# igvv.net
KiCad netlist of a schematic drawn in EAGLE
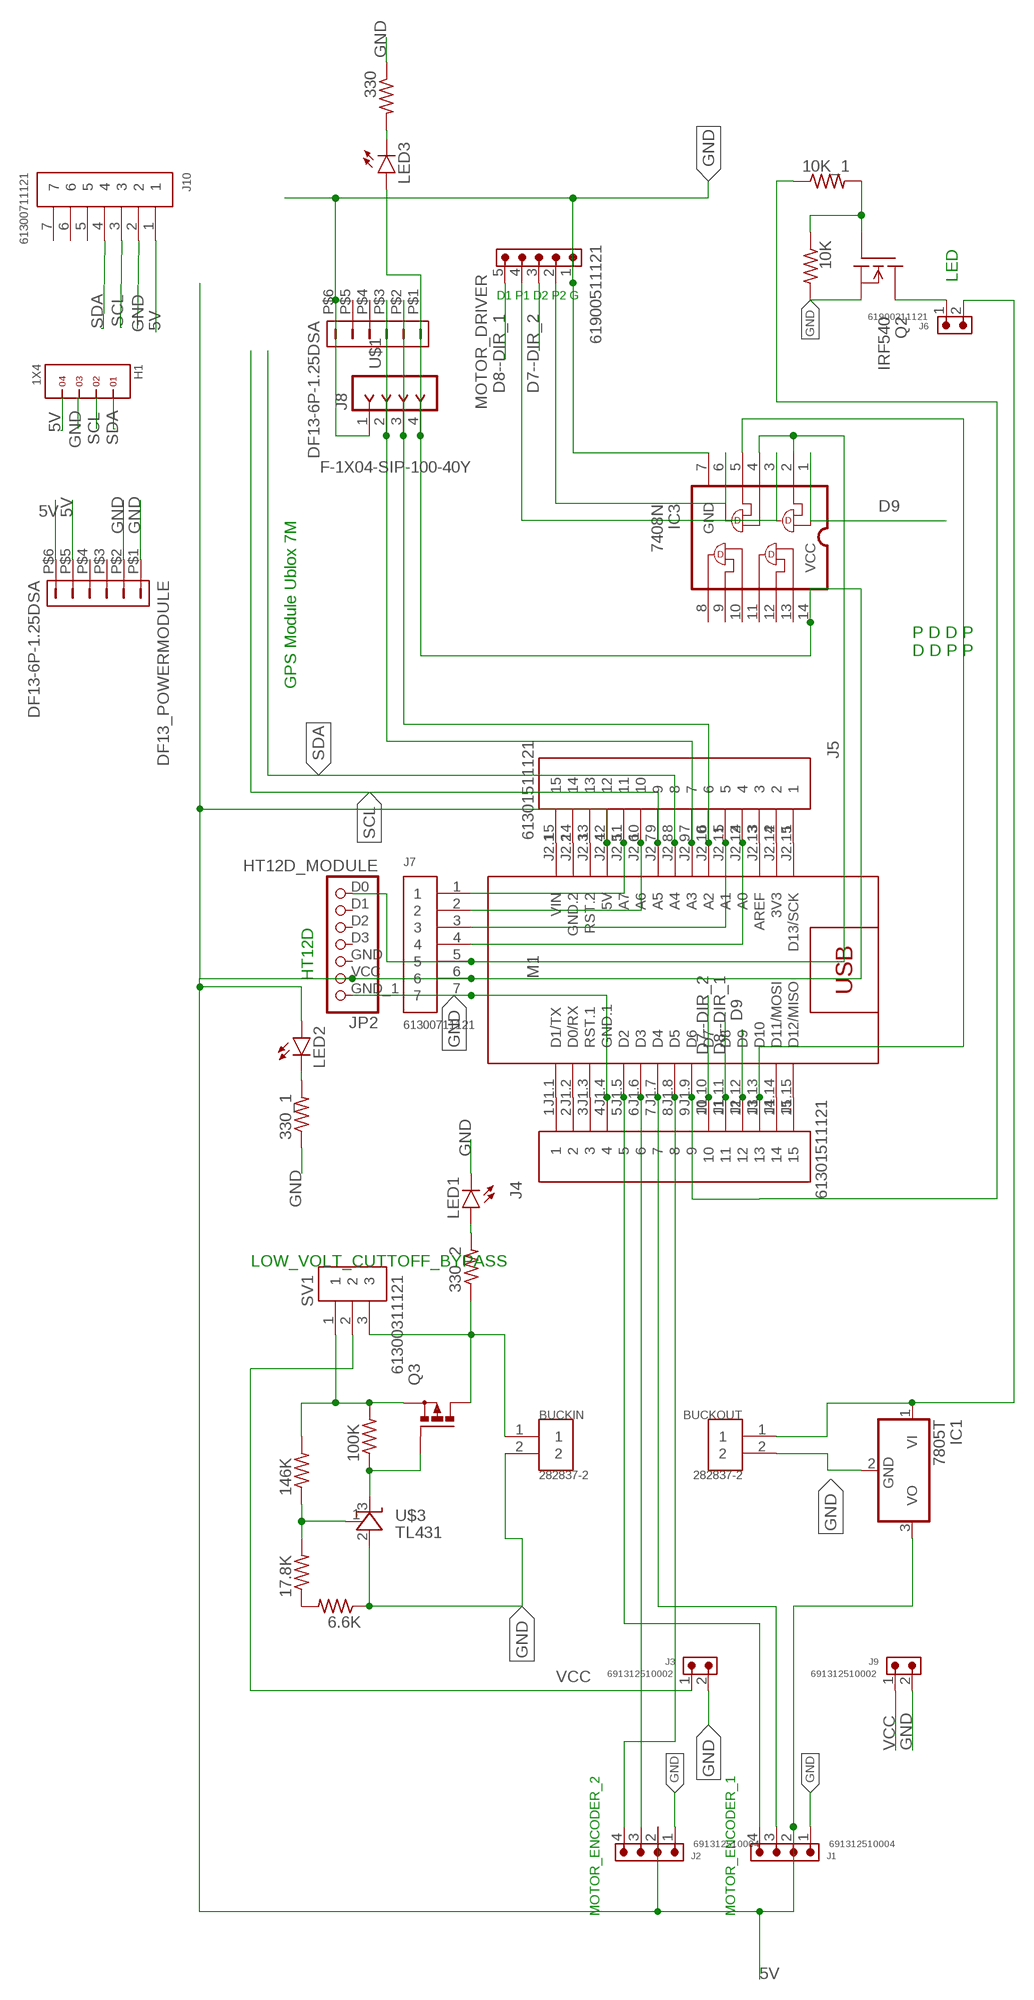
[diagram p0: schematic, sheet 1]

(export (version "E")
  (design (tool "Eeschema 10.0.6"))
  (components
    (comp (ref "6.6K")
      (value "R-US_0207/10")
      (footprint "eagle-import:0207_10")
      (libsource (lib "eagle-import") (part "R-US_0207/10"))
    )
    (comp (ref "10K")
      (value "R-US_0207/10")
      (footprint "eagle-import:0207_10")
      (libsource (lib "eagle-import") (part "R-US_0207/10"))
    )
    (comp (ref "10K_1")
      (value "R-US_0207/10")
      (footprint "eagle-import:0207_10")
      (libsource (lib "eagle-import") (part "R-US_0207/10"))
    )
    (comp (ref "17.8K")
      (value "R-US_0207/10")
      (footprint "eagle-import:0207_10")
      (libsource (lib "eagle-import") (part "R-US_0207/10"))
    )
    (comp (ref "100K")
      (value "R-US_0207/10")
      (footprint "eagle-import:0207_10")
      (libsource (lib "eagle-import") (part "R-US_0207/10"))
    )
    (comp (ref "146K")
      (value "R-US_0207/10")
      (footprint "eagle-import:0207_10")
      (libsource (lib "eagle-import") (part "R-US_0207/10"))
    )
    (comp (ref "330")
      (value "R-US_0207/10")
      (footprint "eagle-import:0207_10")
      (libsource (lib "eagle-import") (part "R-US_0207/10"))
    )
    (comp (ref "330_1")
      (value "R-US_0207/10")
      (footprint "eagle-import:0207_10")
      (libsource (lib "eagle-import") (part "R-US_0207/10"))
    )
    (comp (ref "330_2")
      (value "R-US_0207/10")
      (footprint "eagle-import:0207_10")
      (libsource (lib "eagle-import") (part "R-US_0207/10"))
    )
    (comp (ref "BUCKIN")
      (value "282837-2")
      (footprint "eagle-import:TE_282837-2")
      (fields (field (name "MF") "TE Connectivity"))
      (libsource (lib "eagle-import") (part "282837-2"))
    )
    (comp (ref "BUCKOUT")
      (value "282837-2")
      (footprint "eagle-import:TE_282837-2")
      (fields (field (name "MF") "TE Connectivity"))
      (libsource (lib "eagle-import") (part "282837-2"))
    )
    (comp (ref "DF13_POWERMODULE")
      (value "DF13-6P-1.25DSA")
      (footprint "eagle-import:DF13-6P-1.25DSA")
      (libsource (lib "eagle-import") (part "DF13-6P-1.25DSA"))
    )
    (comp (ref "H1")
      (value "1X4")
      (footprint "eagle-import:1X4")
      (libsource (lib "eagle-import") (part "1X4"))
    )
    (comp (ref "IC1")
      (value "7805T")
      (footprint "eagle-import:TO220H")
      (libsource (lib "eagle-import") (part "7805T"))
    )
    (comp (ref "IC3")
      (value "7408N")
      (footprint "eagle-import:DIL14")
      (libsource (lib "eagle-import") (part "7408N"))
    )
    (comp (ref "J1")
      (value "691312510004")
      (footprint "eagle-import:691312510004")
      (libsource (lib "eagle-import") (part "691312510004"))
    )
    (comp (ref "J2")
      (value "691312510004")
      (footprint "eagle-import:691312510004")
      (libsource (lib "eagle-import") (part "691312510004"))
    )
    (comp (ref "J3")
      (value "691312510002")
      (footprint "eagle-import:691312510002")
      (libsource (lib "eagle-import") (part "691312510002"))
    )
    (comp (ref "J4")
      (value "61301511121")
      (footprint "eagle-import:61301511121")
      (fields
        (field (name "DIGIKEY_PART_NUMBER") "732-5326-ND")
        (field (name "MANUFACTURER") "Wurth Electronics Inc.")
        (field (name "CREATED_BY") "PCBLayout.com")
      )
      (libsource (lib "eagle-import") (part "61301511121"))
    )
    (comp (ref "J5")
      (value "61301511121")
      (footprint "eagle-import:61301511121")
      (fields
        (field (name "DIGIKEY_PART_NUMBER") "732-5326-ND")
        (field (name "MANUFACTURER") "Wurth Electronics Inc.")
        (field (name "CREATED_BY") "PCBLayout.com")
      )
      (libsource (lib "eagle-import") (part "61301511121"))
    )
    (comp (ref "J6")
      (value "61900211121")
      (footprint "eagle-import:61900211121")
      (libsource (lib "eagle-import") (part "61900211121"))
    )
    (comp (ref "J7")
      (value "61300711121")
      (footprint "eagle-import:61300711121")
      (fields
        (field (name "DIGI_KEY_PART_NUMBER") "732-5320-ND")
        (field (name "MANUFACTURER") "Wurth Electronics Inc.")
        (field (name "CREATED_BY") "PCBLayout.com")
      )
      (libsource (lib "eagle-import") (part "61300711121"))
    )
    (comp (ref "J8")
      (value "F-1X04-SIP-100-40Y")
      (footprint "eagle-import:SIP-100-04-40Y")
      (libsource (lib "eagle-import") (part "F-1X04-SIP-100-40Y"))
    )
    (comp (ref "J9")
      (value "691312510002")
      (footprint "eagle-import:691312510002")
      (libsource (lib "eagle-import") (part "691312510002"))
    )
    (comp (ref "J10")
      (value "61300711121")
      (footprint "eagle-import:61300711121")
      (fields
        (field (name "DIGI_KEY_PART_NUMBER") "732-5320-ND")
        (field (name "MANUFACTURER") "Wurth Electronics Inc.")
        (field (name "CREATED_BY") "PCBLayout.com")
      )
      (libsource (lib "eagle-import") (part "61300711121"))
    )
    (comp (ref "JP2")
      (value "HT12D_MODULE")
      (footprint "eagle-import:HT12D_MODULE")
      (libsource (lib "eagle-import") (part "HT12D_MODULE"))
    )
    (comp (ref "LED1")
      (value "LED5MM")
      (footprint "eagle-import:LED5MM")
      (libsource (lib "eagle-import") (part "LED5MM"))
    )
    (comp (ref "LED2")
      (value "LED5MM")
      (footprint "eagle-import:LED5MM")
      (libsource (lib "eagle-import") (part "LED5MM"))
    )
    (comp (ref "LED3")
      (value "LED5MM")
      (footprint "eagle-import:LED5MM")
      (libsource (lib "eagle-import") (part "LED5MM"))
    )
    (comp (ref "M1")
      (value "ARDUINO-NANO-3.0ARDUINO-NANO-3.0")
      (footprint "eagle-import:ARDUINO-NANO-3.0")
      (libsource (lib "eagle-import") (part "ARDUINO-NANO-3.0ARDUINO-NANO-3.0"))
    )
    (comp (ref "MOTOR_DRIVER")
      (value "61900511121")
      (footprint "eagle-import:61900511121")
      (libsource (lib "eagle-import") (part "61900511121"))
    )
    (comp (ref "Q2")
      (value "IRF540")
      (footprint "eagle-import:TO220")
      (libsource (lib "eagle-import") (part "IRF540"))
    )
    (comp (ref "Q3")
      (value "PMOSFET_PTO220BV")
      (footprint "eagle-import:TO220BV")
      (libsource (lib "eagle-import") (part "PMOSFET_PTO220BV"))
    )
    (comp (ref "SV1")
      (value "61300311121")
      (footprint "eagle-import:61300311121")
      (fields
        (field (name "DIGI_KEY_PART_NUMBER") "732-5316-ND")
        (field (name "MANUFACTURER") "Wurth Electronics Inc.")
        (field (name "CREATED_BY") "PCBLayout.com")
      )
      (libsource (lib "eagle-import") (part "61300311121"))
    )
    (comp (ref "U$1")
      (value "DF13-6P-1.25DSA")
      (footprint "eagle-import:DF13-6P-1.25DSA")
      (libsource (lib "eagle-import") (part "DF13-6P-1.25DSA"))
    )
    (comp (ref "U$3")
      (value "TL431")
      (footprint "eagle-import:TO-92")
      (libsource (lib "eagle-import") (part "TL431"))
    )
  )
  (nets
    (net (code "1") (name "/5V") (class "Default")
      (node (ref "DF13_POWERMODULE") (pin "P$5") (pinfunction "5_P$5") (pintype "passive"))
      (node (ref "DF13_POWERMODULE") (pin "P$6") (pinfunction "6_P$6") (pintype "passive"))
      (node (ref "H1") (pin "4") (pinfunction "4_4") (pintype "bidirectional"))
      (node (ref "IC1") (pin "3") (pinfunction "VO_3") (pintype "passive"))
      (node (ref "IC3") (pin "14") (pinfunction "VCC_14") (pintype "bidirectional"))
      (node (ref "J1") (pin "2") (pinfunction "2_2") (pintype "passive"))
      (node (ref "J10") (pin "1") (pinfunction "1_1") (pintype "passive"))
      (node (ref "J2") (pin "2") (pinfunction "2_2") (pintype "passive"))
      (node (ref "J5") (pin "12") (pinfunction "12_12") (pintype "passive"))
      (node (ref "J7") (pin "6") (pinfunction "6_6") (pintype "passive"))
      (node (ref "J8") (pin "4") (pinfunction "4_4") (pintype "passive"))
      (node (ref "JP2") (pin "VCC") (pinfunction "2_VCC") (pintype "passive"))
      (node (ref "LED2") (pin "A") (pinfunction "A_A") (pintype "passive"))
      (node (ref "LED3") (pin "A") (pinfunction "A_A") (pintype "passive"))
      (node (ref "M1") (pin "J2.4") (pinfunction "5V_J2.4") (pintype "power_in"))
      (node (ref "U$1") (pin "P$1") (pinfunction "1_P$1") (pintype "passive"))
    )
    (net (code "2") (name "/D7--DIR_2") (class "Default")
      (node (ref "J4") (pin "10") (pinfunction "10_10") (pintype "passive"))
      (node (ref "M1") (pin "J1.10") (pinfunction "D7_J1.10") (pintype "bidirectional"))
      (node (ref "MOTOR_DRIVER") (pin "3") (pinfunction "3_3") (pintype "passive"))
    )
    (net (code "3") (name "/D8--DIR_1") (class "Default")
      (node (ref "J4") (pin "11") (pinfunction "11_11") (pintype "passive"))
      (node (ref "M1") (pin "J1.11") (pinfunction "D8_J1.11") (pintype "bidirectional"))
      (node (ref "MOTOR_DRIVER") (pin "5") (pinfunction "5_5") (pintype "passive"))
    )
    (net (code "4") (name "/D9") (class "Default")
      (node (ref "IC3") (pin "1") (pinfunction "P$1_1") (pintype "bidirectional"))
      (node (ref "J4") (pin "12") (pinfunction "12_12") (pintype "passive"))
      (node (ref "M1") (pin "J1.12") (pinfunction "D9_J1.12") (pintype "bidirectional"))
    )
    (net (code "5") (name "/VCC") (class "Default")
      (node (ref "J3") (pin "1") (pinfunction "1_1") (pintype "passive"))
      (node (ref "J9") (pin "1") (pinfunction "1_1") (pintype "passive"))
      (node (ref "SV1") (pin "2") (pinfunction "2_2") (pintype "passive"))
    )
    (net (code "6") (name "GND") (class "Default")
      (node (ref "10K") (pin "2") (pinfunction "2_2") (pintype "passive"))
      (node (ref "330") (pin "1") (pinfunction "1_1") (pintype "passive"))
      (node (ref "330_1") (pin "1") (pinfunction "1_1") (pintype "passive"))
      (node (ref "6.6K") (pin "1") (pinfunction "1_1") (pintype "passive"))
      (node (ref "BUCKIN") (pin "2") (pinfunction "2_2") (pintype "passive"))
      (node (ref "BUCKOUT") (pin "2") (pinfunction "2_2") (pintype "passive"))
      (node (ref "DF13_POWERMODULE") (pin "P$1") (pinfunction "1_P$1") (pintype "passive"))
      (node (ref "DF13_POWERMODULE") (pin "P$2") (pinfunction "2_P$2") (pintype "passive"))
      (node (ref "H1") (pin "3") (pinfunction "3_3") (pintype "bidirectional"))
      (node (ref "IC1") (pin "2") (pinfunction "GND_2") (pintype "passive"))
      (node (ref "IC3") (pin "7") (pinfunction "GND_7") (pintype "bidirectional"))
      (node (ref "J1") (pin "1") (pinfunction "1_1") (pintype "passive"))
      (node (ref "J10") (pin "2") (pinfunction "2_2") (pintype "passive"))
      (node (ref "J2") (pin "1") (pinfunction "1_1") (pintype "passive"))
      (node (ref "J3") (pin "2") (pinfunction "2_2") (pintype "passive"))
      (node (ref "J4") (pin "4") (pinfunction "4_4") (pintype "passive"))
      (node (ref "J7") (pin "7") (pinfunction "7_7") (pintype "passive"))
      (node (ref "J8") (pin "1") (pinfunction "1_1") (pintype "passive"))
      (node (ref "J9") (pin "2") (pinfunction "2_2") (pintype "passive"))
      (node (ref "JP2") (pin "GND_1") (pinfunction "1_GND_1") (pintype "passive"))
      (node (ref "LED1") (pin "K") (pinfunction "C_K") (pintype "passive"))
      (node (ref "M1") (pin "J1.4") (pinfunction "GND.1_J1.4") (pintype "power_in"))
      (node (ref "MOTOR_DRIVER") (pin "1") (pinfunction "1_1") (pintype "passive"))
      (node (ref "Q2") (pin "3") (pinfunction "S_3") (pintype "passive"))
      (node (ref "U$1") (pin "P$6") (pinfunction "6_P$6") (pintype "passive"))
      (node (ref "U$3") (pin "2") (pinfunction "A_2") (pintype "bidirectional"))
    )
    (net (code "7") (name "Net-(17.8K-Pad1)") (class "Default")
      (node (ref "17.8K") (pin "1") (pinfunction "1_1") (pintype "passive"))
      (node (ref "6.6K") (pin "2") (pinfunction "2_2") (pintype "passive"))
    )
    (net (code "8") (name "Net-(100K-Pad2)") (class "Default")
      (node (ref "100K") (pin "2") (pinfunction "2_2") (pintype "passive"))
      (node (ref "146K") (pin "2") (pinfunction "2_2") (pintype "passive"))
      (node (ref "Q3") (pin "S") (pinfunction "S_S") (pintype "passive"))
      (node (ref "SV1") (pin "1") (pinfunction "1_1") (pintype "passive"))
    )
    (net (code "9") (name "Net-(330_2-Pad1)") (class "Default")
      (node (ref "330_2") (pin "1") (pinfunction "1_1") (pintype "passive"))
      (node (ref "BUCKIN") (pin "1") (pinfunction "1_1") (pintype "passive"))
      (node (ref "Q3") (pin "D") (pinfunction "D_D") (pintype "passive"))
      (node (ref "SV1") (pin "3") (pinfunction "3_3") (pintype "passive"))
    )
    (net (code "10") (name "Net-(330_2-Pad2)") (class "Default")
      (node (ref "330_2") (pin "2") (pinfunction "2_2") (pintype "passive"))
      (node (ref "LED1") (pin "A") (pinfunction "A_A") (pintype "passive"))
    )
    (net (code "11") (name "Net-(IC1-VI)") (class "Default")
      (node (ref "BUCKOUT") (pin "1") (pinfunction "1_1") (pintype "passive"))
      (node (ref "IC1") (pin "1") (pinfunction "VI_1") (pintype "input"))
      (node (ref "J6") (pin "2") (pinfunction "2_2") (pintype "passive"))
    )
    (net (code "12") (name "Net-(IC3-P$2)") (class "Default")
      (node (ref "IC3") (pin "2") (pinfunction "P$2_2") (pintype "bidirectional"))
      (node (ref "IC3") (pin "4") (pinfunction "P$4_4") (pintype "bidirectional"))
      (node (ref "J7") (pin "5") (pinfunction "5_5") (pintype "passive"))
      (node (ref "JP2") (pin "D0") (pinfunction "7_D0") (pintype "passive"))
    )
    (net (code "13") (name "Net-(IC3-P$3)") (class "Default")
      (node (ref "IC3") (pin "3") (pinfunction "P$3_3") (pintype "bidirectional"))
      (node (ref "MOTOR_DRIVER") (pin "4") (pinfunction "4_4") (pintype "passive"))
    )
    (net (code "14") (name "Net-(IC3-P$5)") (class "Default")
      (node (ref "IC3") (pin "5") (pinfunction "P$5_5") (pintype "bidirectional"))
      (node (ref "J4") (pin "13") (pinfunction "13_13") (pintype "passive"))
      (node (ref "M1") (pin "J1.13") (pinfunction "D10_J1.13") (pintype "bidirectional"))
    )
    (net (code "15") (name "Net-(IC3-P$6)") (class "Default")
      (node (ref "IC3") (pin "6") (pinfunction "P$6_6") (pintype "bidirectional"))
      (node (ref "MOTOR_DRIVER") (pin "2") (pinfunction "2_2") (pintype "passive"))
    )
    (net (code "16") (name "Net-(LED2-C)") (class "Default")
      (node (ref "330_1") (pin "2") (pinfunction "2_2") (pintype "passive"))
      (node (ref "LED2") (pin "K") (pinfunction "C_K") (pintype "passive"))
    )
    (net (code "17") (name "Net-(LED3-C)") (class "Default")
      (node (ref "330") (pin "2") (pinfunction "2_2") (pintype "passive"))
      (node (ref "LED3") (pin "K") (pinfunction "C_K") (pintype "passive"))
    )
    (net (code "18") (name "Net-(M1-3V3)") (class "Default")
      (node (ref "J5") (pin "2") (pinfunction "2_2") (pintype "passive"))
      (node (ref "M1") (pin "J2.14") (pinfunction "3V3_J2.14") (pintype "power_in"))
    )
    (net (code "19") (name "Net-(M1-A0)") (class "Default")
      (node (ref "J5") (pin "4") (pinfunction "4_4") (pintype "passive"))
      (node (ref "J7") (pin "4") (pinfunction "4_4") (pintype "passive"))
      (node (ref "M1") (pin "J2.12") (pinfunction "A0_J2.12") (pintype "bidirectional"))
    )
    (net (code "20") (name "Net-(M1-A1)") (class "Default")
      (node (ref "J5") (pin "5") (pinfunction "5_5") (pintype "passive"))
      (node (ref "J7") (pin "3") (pinfunction "3_3") (pintype "passive"))
      (node (ref "M1") (pin "J2.11") (pinfunction "A1_J2.11") (pintype "bidirectional"))
    )
    (net (code "21") (name "Net-(M1-A2)") (class "Default")
      (node (ref "J5") (pin "6") (pinfunction "6_6") (pintype "passive"))
      (node (ref "J8") (pin "3") (pinfunction "3_3") (pintype "passive"))
      (node (ref "M1") (pin "J2.10") (pinfunction "A2_J2.10") (pintype "bidirectional"))
      (node (ref "U$1") (pin "P$2") (pinfunction "2_P$2") (pintype "passive"))
    )
    (net (code "22") (name "Net-(M1-A3)") (class "Default")
      (node (ref "J5") (pin "7") (pinfunction "7_7") (pintype "passive"))
      (node (ref "J8") (pin "2") (pinfunction "2_2") (pintype "passive"))
      (node (ref "M1") (pin "J2.9") (pinfunction "A3_J2.9") (pintype "bidirectional"))
      (node (ref "U$1") (pin "P$3") (pinfunction "3_P$3") (pintype "passive"))
    )
    (net (code "23") (name "Net-(M1-A6)") (class "Default")
      (node (ref "J5") (pin "10") (pinfunction "10_10") (pintype "passive"))
      (node (ref "J7") (pin "2") (pinfunction "2_2") (pintype "passive"))
      (node (ref "M1") (pin "J2.6") (pinfunction "A6_J2.6") (pintype "bidirectional"))
    )
    (net (code "24") (name "Net-(M1-A7)") (class "Default")
      (node (ref "J5") (pin "11") (pinfunction "11_11") (pintype "passive"))
      (node (ref "J7") (pin "1") (pinfunction "1_1") (pintype "passive"))
      (node (ref "M1") (pin "J2.5") (pinfunction "A7_J2.5") (pintype "bidirectional"))
    )
    (net (code "25") (name "Net-(M1-AREF)") (class "Default")
      (node (ref "J5") (pin "3") (pinfunction "3_3") (pintype "passive"))
      (node (ref "M1") (pin "J2.13") (pinfunction "AREF_J2.13") (pintype "bidirectional"))
    )
    (net (code "26") (name "Net-(M1-D0{slash}RX)") (class "Default")
      (node (ref "J4") (pin "2") (pinfunction "2_2") (pintype "passive"))
      (node (ref "M1") (pin "J1.2") (pinfunction "D0/RX_J1.2") (pintype "bidirectional"))
    )
    (net (code "27") (name "Net-(M1-D1{slash}TX)") (class "Default")
      (node (ref "J4") (pin "1") (pinfunction "1_1") (pintype "passive"))
      (node (ref "M1") (pin "J1.1") (pinfunction "D1/TX_J1.1") (pintype "bidirectional"))
    )
    (net (code "28") (name "Net-(M1-D2)") (class "Default")
      (node (ref "J1") (pin "4") (pinfunction "4_4") (pintype "passive"))
      (node (ref "J4") (pin "5") (pinfunction "5_5") (pintype "passive"))
      (node (ref "M1") (pin "J1.5") (pinfunction "D2_J1.5") (pintype "bidirectional"))
    )
    (net (code "29") (name "Net-(M1-D3)") (class "Default")
      (node (ref "J2") (pin "3") (pinfunction "3_3") (pintype "passive"))
      (node (ref "J4") (pin "6") (pinfunction "6_6") (pintype "passive"))
      (node (ref "M1") (pin "J1.6") (pinfunction "D3_J1.6") (pintype "bidirectional"))
    )
    (net (code "30") (name "Net-(M1-D4)") (class "Default")
      (node (ref "J1") (pin "3") (pinfunction "3_3") (pintype "passive"))
      (node (ref "J4") (pin "7") (pinfunction "7_7") (pintype "passive"))
      (node (ref "M1") (pin "J1.7") (pinfunction "D4_J1.7") (pintype "bidirectional"))
    )
    (net (code "31") (name "Net-(M1-D5)") (class "Default")
      (node (ref "J2") (pin "4") (pinfunction "4_4") (pintype "passive"))
      (node (ref "J4") (pin "8") (pinfunction "8_8") (pintype "passive"))
      (node (ref "M1") (pin "J1.8") (pinfunction "D5_J1.8") (pintype "bidirectional"))
    )
    (net (code "32") (name "Net-(M1-D6)") (class "Default")
      (node (ref "10K_1") (pin "1") (pinfunction "1_1") (pintype "passive"))
      (node (ref "J4") (pin "9") (pinfunction "9_9") (pintype "passive"))
      (node (ref "M1") (pin "J1.9") (pinfunction "D6_J1.9") (pintype "bidirectional"))
    )
    (net (code "33") (name "Net-(M1-D11{slash}MOSI)") (class "Default")
      (node (ref "J4") (pin "14") (pinfunction "14_14") (pintype "passive"))
      (node (ref "M1") (pin "J1.14") (pinfunction "D11/MOSI_J1.14") (pintype "bidirectional"))
    )
    (net (code "34") (name "Net-(M1-D12{slash}MISO)") (class "Default")
      (node (ref "J4") (pin "15") (pinfunction "15_15") (pintype "passive"))
      (node (ref "M1") (pin "J1.15") (pinfunction "D12/MISO_J1.15") (pintype "bidirectional"))
    )
    (net (code "35") (name "Net-(M1-D13{slash}SCK)") (class "Default")
      (node (ref "J5") (pin "1") (pinfunction "1_1") (pintype "passive"))
      (node (ref "M1") (pin "J2.15") (pinfunction "D13/SCK_J2.15") (pintype "bidirectional"))
    )
    (net (code "36") (name "Net-(M1-GND.2)") (class "Default")
      (node (ref "J5") (pin "14") (pinfunction "14_14") (pintype "passive"))
      (node (ref "M1") (pin "J2.2") (pinfunction "GND.2_J2.2") (pintype "power_in"))
    )
    (net (code "37") (name "Net-(M1-RST.1)") (class "Default")
      (node (ref "J4") (pin "3") (pinfunction "3_3") (pintype "passive"))
      (node (ref "M1") (pin "J1.3") (pinfunction "RST.1_J1.3") (pintype "bidirectional"))
    )
    (net (code "38") (name "Net-(M1-RST.2)") (class "Default")
      (node (ref "J5") (pin "13") (pinfunction "13_13") (pintype "passive"))
      (node (ref "M1") (pin "J2.3") (pinfunction "RST.2_J2.3") (pintype "bidirectional"))
    )
    (net (code "39") (name "Net-(M1-VIN)") (class "Default")
      (node (ref "J5") (pin "15") (pinfunction "15_15") (pintype "passive"))
      (node (ref "M1") (pin "J2.1") (pinfunction "VIN_J2.1") (pintype "power_in"))
    )
    (net (code "40") (name "Net-(Q2-D)") (class "Default")
      (node (ref "J6") (pin "1") (pinfunction "1_1") (pintype "passive"))
      (node (ref "Q2") (pin "2") (pinfunction "D_2") (pintype "passive"))
    )
    (net (code "41") (name "Net-(Q2-G)") (class "Default")
      (node (ref "10K") (pin "1") (pinfunction "1_1") (pintype "passive"))
      (node (ref "10K_1") (pin "2") (pinfunction "2_2") (pintype "passive"))
      (node (ref "Q2") (pin "1") (pinfunction "G_1") (pintype "passive"))
    )
    (net (code "42") (name "Net-(U$3-C)") (class "Default")
      (node (ref "100K") (pin "1") (pinfunction "1_1") (pintype "passive"))
      (node (ref "Q3") (pin "G") (pinfunction "G_G") (pintype "passive"))
      (node (ref "U$3") (pin "3") (pinfunction "C_3") (pintype "bidirectional"))
    )
    (net (code "43") (name "Net-(U$3-REF)") (class "Default")
      (node (ref "146K") (pin "1") (pinfunction "1_1") (pintype "passive"))
      (node (ref "17.8K") (pin "2") (pinfunction "2_2") (pintype "passive"))
      (node (ref "U$3") (pin "1") (pinfunction "REF_1") (pintype "input"))
    )
    (net (code "44") (name "SCL") (class "Default")
      (node (ref "H1") (pin "2") (pinfunction "2_2") (pintype "bidirectional"))
      (node (ref "J10") (pin "3") (pinfunction "3_3") (pintype "passive"))
      (node (ref "J5") (pin "9") (pinfunction "9_9") (pintype "passive"))
      (node (ref "M1") (pin "J2.7") (pinfunction "A5_J2.7") (pintype "bidirectional"))
    )
    (net (code "45") (name "SDA") (class "Default")
      (node (ref "H1") (pin "1") (pinfunction "1_1") (pintype "bidirectional"))
      (node (ref "J10") (pin "4") (pinfunction "4_4") (pintype "passive"))
      (node (ref "J5") (pin "8") (pinfunction "8_8") (pintype "passive"))
      (node (ref "M1") (pin "J2.8") (pinfunction "A4_J2.8") (pintype "bidirectional"))
    )
    (net (code "46") (name "unconnected-(DF13_POWERMODULE-3-PadP$3)") (class "Default")
      (node (ref "DF13_POWERMODULE") (pin "P$3") (pinfunction "3_P$3") (pintype "passive"))
    )
    (net (code "47") (name "unconnected-(DF13_POWERMODULE-4-PadP$4)") (class "Default")
      (node (ref "DF13_POWERMODULE") (pin "P$4") (pinfunction "4_P$4") (pintype "passive"))
    )
    (net (code "48") (name "unconnected-(IC3-P$8-Pad8)") (class "Default")
      (node (ref "IC3") (pin "8") (pinfunction "P$8_8") (pintype "bidirectional"))
    )
    (net (code "49") (name "unconnected-(IC3-P$9-Pad9)") (class "Default")
      (node (ref "IC3") (pin "9") (pinfunction "P$9_9") (pintype "bidirectional"))
    )
    (net (code "50") (name "unconnected-(IC3-P$10-Pad10)") (class "Default")
      (node (ref "IC3") (pin "10") (pinfunction "P$10_10") (pintype "bidirectional"))
    )
    (net (code "51") (name "unconnected-(IC3-P$11-Pad11)") (class "Default")
      (node (ref "IC3") (pin "11") (pinfunction "P$11_11") (pintype "bidirectional"))
    )
    (net (code "52") (name "unconnected-(IC3-P$12-Pad12)") (class "Default")
      (node (ref "IC3") (pin "12") (pinfunction "P$12_12") (pintype "bidirectional"))
    )
    (net (code "53") (name "unconnected-(IC3-P$13-Pad13)") (class "Default")
      (node (ref "IC3") (pin "13") (pinfunction "P$13_13") (pintype "bidirectional"))
    )
    (net (code "54") (name "unconnected-(J10-Pad5)") (class "Default")
      (node (ref "J10") (pin "5") (pinfunction "5_5") (pintype "passive"))
    )
    (net (code "55") (name "unconnected-(J10-Pad6)") (class "Default")
      (node (ref "J10") (pin "6") (pinfunction "6_6") (pintype "passive"))
    )
    (net (code "56") (name "unconnected-(J10-Pad7)") (class "Default")
      (node (ref "J10") (pin "7") (pinfunction "7_7") (pintype "passive"))
    )
    (net (code "57") (name "unconnected-(JP2-3-PadGND)") (class "Default")
      (node (ref "JP2") (pin "GND") (pinfunction "3_GND") (pintype "passive"))
    )
    (net (code "58") (name "unconnected-(JP2-4-PadD3)") (class "Default")
      (node (ref "JP2") (pin "D3") (pinfunction "4_D3") (pintype "passive"))
    )
    (net (code "59") (name "unconnected-(JP2-5-PadD2)") (class "Default")
      (node (ref "JP2") (pin "D2") (pinfunction "5_D2") (pintype "passive"))
    )
    (net (code "60") (name "unconnected-(JP2-6-PadD1)") (class "Default")
      (node (ref "JP2") (pin "D1") (pinfunction "6_D1") (pintype "passive"))
    )
    (net (code "61") (name "unconnected-(U$1-4-PadP$4)") (class "Default")
      (node (ref "U$1") (pin "P$4") (pinfunction "4_P$4") (pintype "passive"))
    )
    (net (code "62") (name "unconnected-(U$1-5-PadP$5)") (class "Default")
      (node (ref "U$1") (pin "P$5") (pinfunction "5_P$5") (pintype "passive"))
    )
  )
)
